# HeadlightPCB.net
KiCad netlist of a schematic drawn in EAGLE
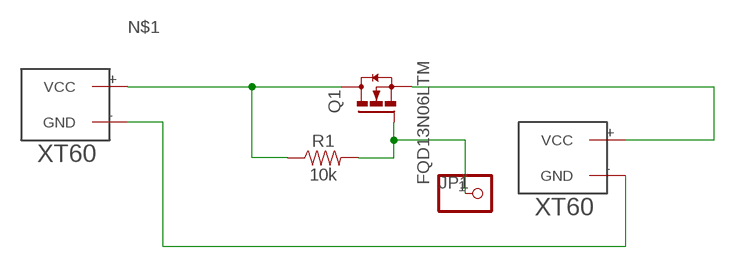
[diagram p0: schematic, sheet 1]

(export (version "E")
  (design (tool "Eeschema 10.0.6"))
  (components
    (comp (ref "JP1")
      (value "PINHD-1X1")
      (footprint "eagle-import:1X01")
      (libsource (lib "eagle-import") (part "PINHD-1X1"))
    )
    (comp (ref "Q1")
      (value "FQD13N06LTM")
      (footprint "eagle-import:DPAK4")
      (fields
        (field (name "DIGIKEY_PART_NUMBER") "FQD13N06LTMCT-ND")
        (field (name "MANUFACTURER") "ON Semiconductor")
        (field (name "CREATED_BY") "PCBLayout.com")
      )
      (libsource (lib "eagle-import") (part "FQD13N06LTM"))
    )
    (comp (ref "R1")
      (value "10k")
      (footprint "eagle-import:0603")
      (libsource (lib "eagle-import") (part "10KOHM-0603-1/10W-1%"))
    )
    (comp (ref "U$2")
      (value "XT60")
      (footprint "eagle-import:XT60")
      (libsource (lib "eagle-import") (part "XT60"))
    )
    (comp (ref "VIN")
      (value "XT60")
      (footprint "eagle-import:XT60")
      (libsource (lib "eagle-import") (part "XT60"))
    )
  )
  (nets
    (net (code "1") (name "/N$1") (class "Default")
      (node (ref "Q1") (pin "2") (pinfunction "D_2") (pintype "passive"))
      (node (ref "Q1") (pin "4") (pinfunction "D_4") (pintype "passive"))
      (node (ref "R1") (pin "1") (pinfunction "1_1") (pintype "passive"))
      (node (ref "VIN") (pin "+") (pinfunction "VCC_+") (pintype "bidirectional"))
    )
    (net (code "2") (name "Net-(Q1-G)") (class "Default")
      (node (ref "JP1") (pin "1") (pinfunction "1_1") (pintype "passive"))
      (node (ref "Q1") (pin "1") (pinfunction "G_1") (pintype "passive"))
      (node (ref "R1") (pin "2") (pinfunction "2_2") (pintype "passive"))
    )
    (net (code "3") (name "Net-(Q1-S)") (class "Default")
      (node (ref "Q1") (pin "3") (pinfunction "S_3") (pintype "passive"))
      (node (ref "U$2") (pin "+") (pinfunction "VCC_+") (pintype "bidirectional"))
    )
    (net (code "4") (name "Net-(U$2-GND)") (class "Default")
      (node (ref "U$2") (pin "-") (pinfunction "GND_-") (pintype "bidirectional"))
      (node (ref "VIN") (pin "-") (pinfunction "GND_-") (pintype "bidirectional"))
    )
  )
)
